# wi-fi.net
KiCad netlist of a schematic drawn in Altium Designer
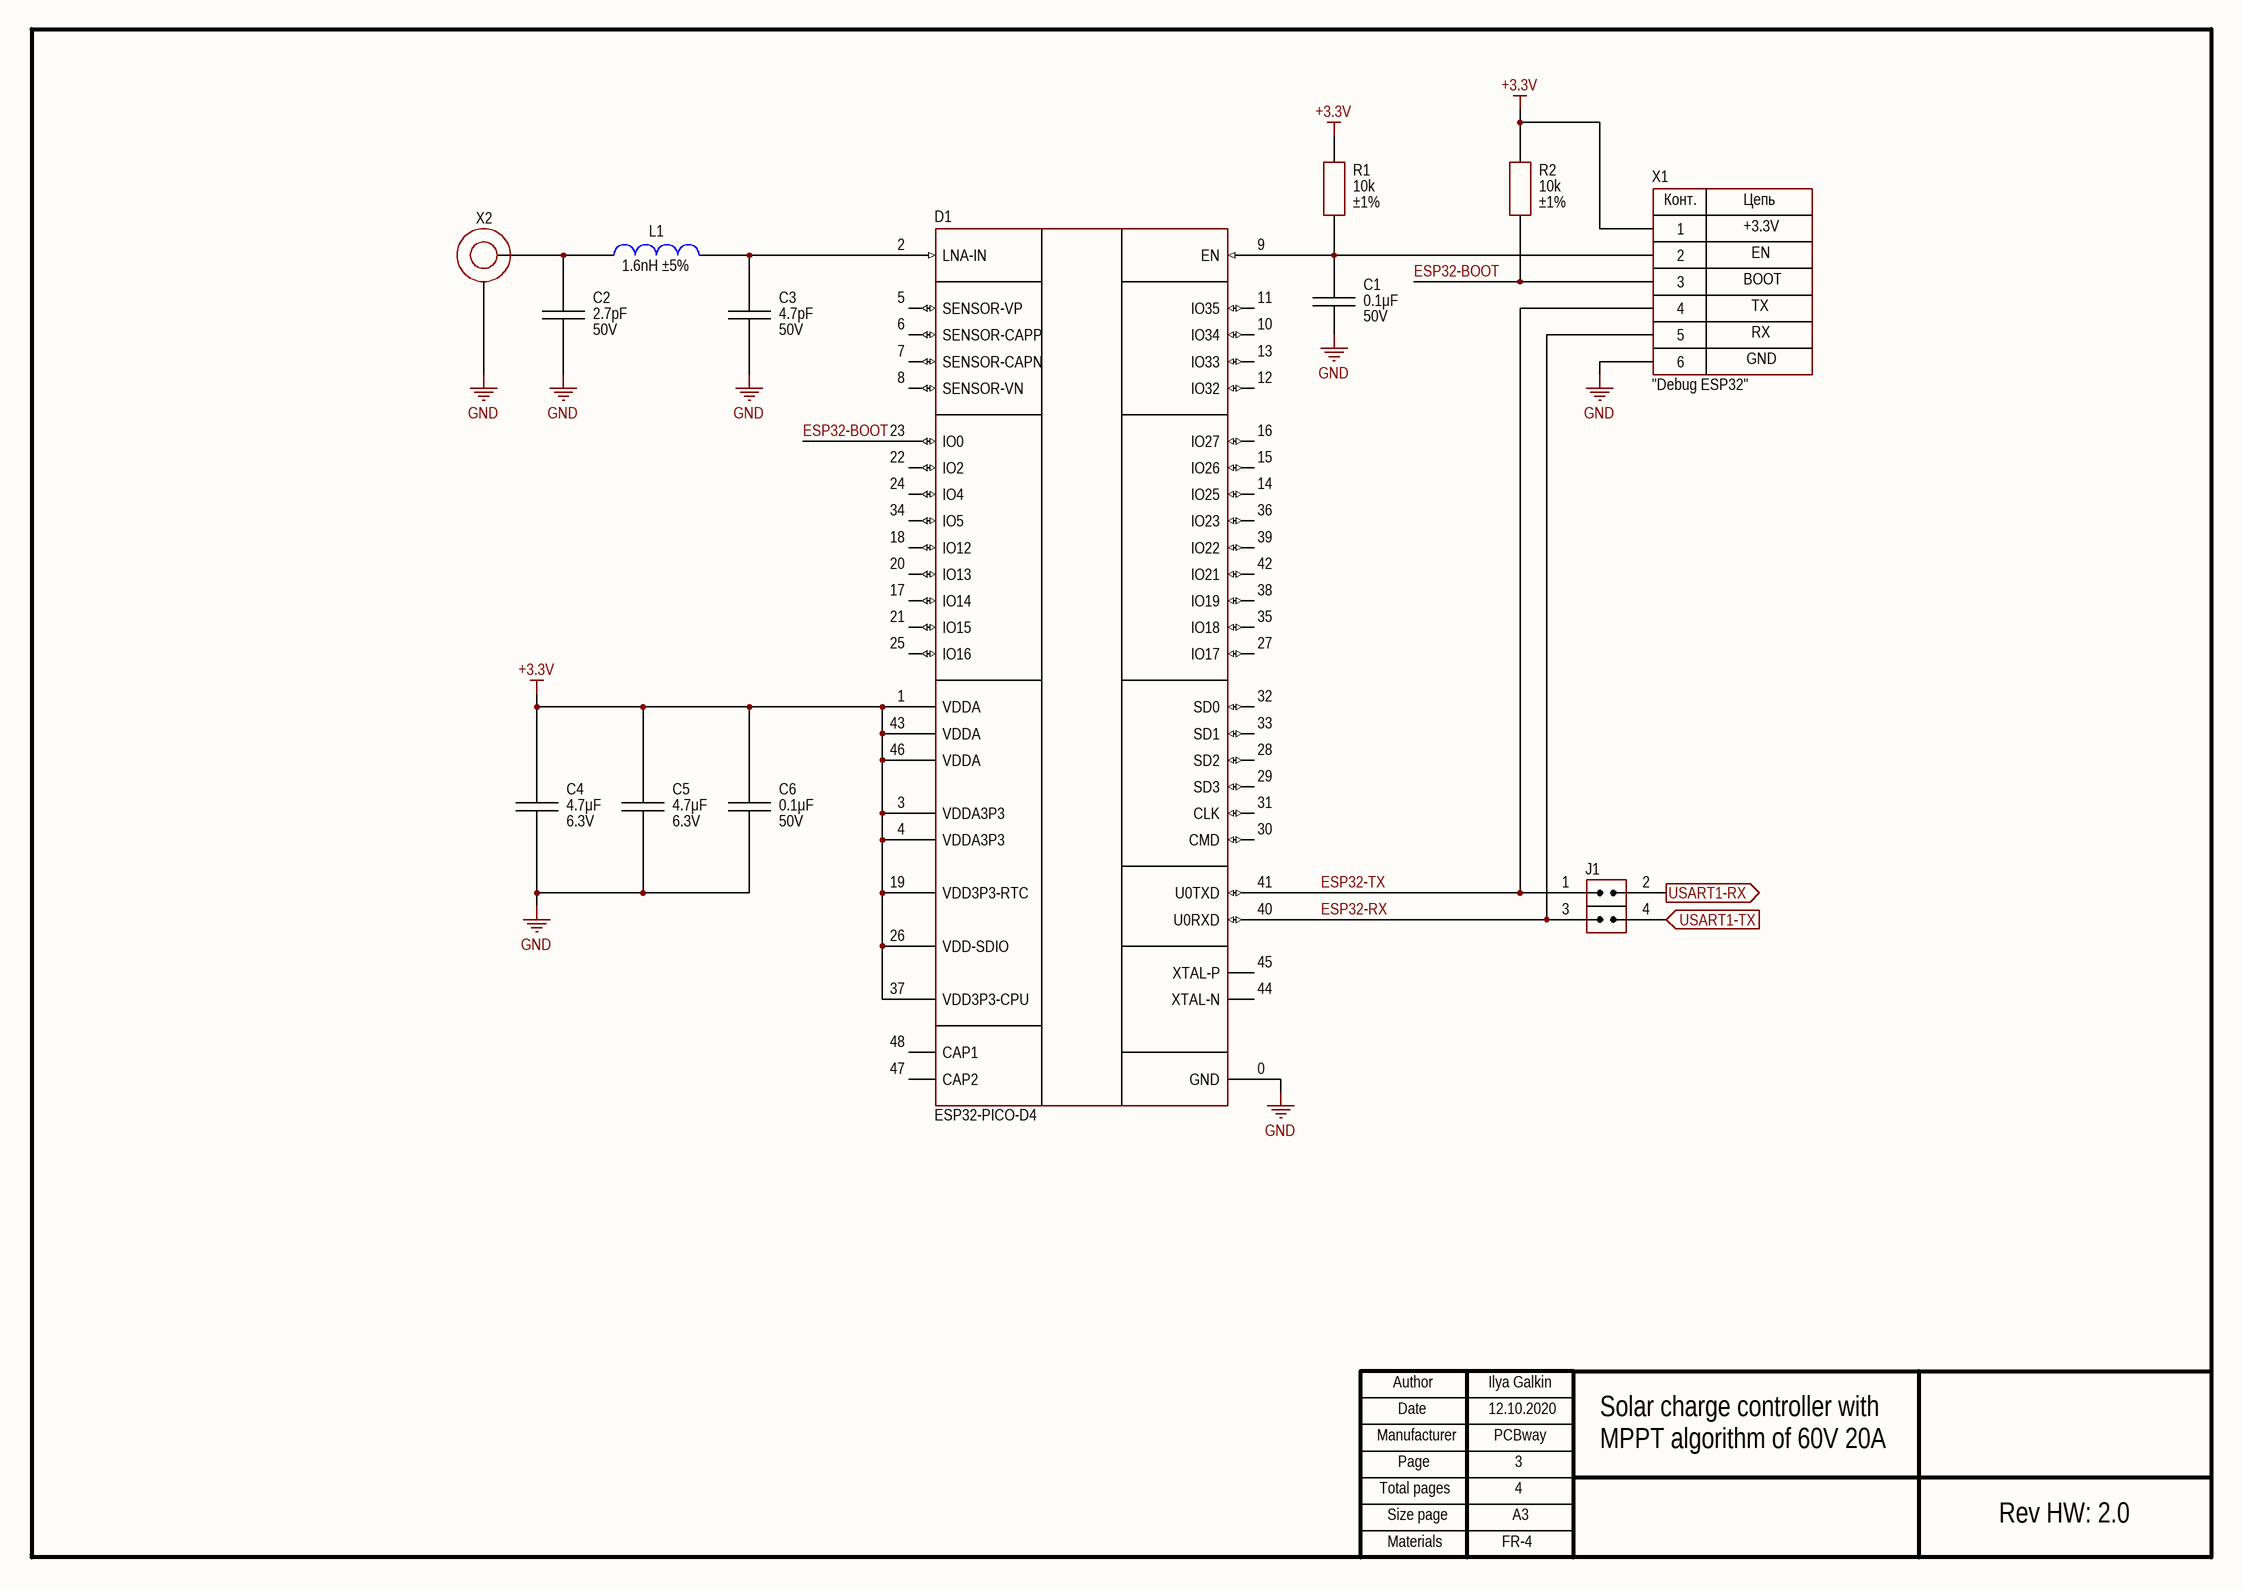
[diagram p0: wi-fi.SchDoc]

(export (version "E")
  (design (tool "Eeschema 10.0.6"))
  (components
    (comp (ref "C1")
      (value "0.1μF")
      (footprint "CAP: 0603")
      (fields
        (field (name "MANUFACTURER") "Samsung")
        (field (name "PARTNUMBER") "CL10B104KB8WPND")
        (field (name "VALUEMANUFACTURERPARTNUMBER") "Ceramic capacitor, 0.1μF, X7R, ±10%, 50V, 0603, -55...+125°C")
        (field (name "VOLTAGE") "50V")
      )
      (libsource (lib "Capacitor") (part "Ceramic_0603"))
    )
    (comp (ref "C2")
      (value "2.7pF")
      (footprint "CAP: 0603")
      (fields
        (field (name "MANUFACTURER") "Samsung")
        (field (name "PARTNUMBER") "CL10C2R7CB81PNC")
        (field (name "VALUEMANUFACTURERPARTNUMBER") "Ceramic capacitor, 2.7pF, NPO, ±0.25pF, 50V, 0603, -55...+125°C")
        (field (name "VOLTAGE") "50V")
      )
      (libsource (lib "capacitor") (part "Ceramic_0603"))
    )
    (comp (ref "C3")
      (value "4.7pF")
      (footprint "CAP: 0603")
      (fields
        (field (name "MANUFACTURER") "Samsung")
        (field (name "PARTNUMBER") "CL10C4R7BB8NNNC")
        (field (name "VALUEMANUFACTURERPARTNUMBER") "Ceramic capacitor, 4.7pF, NPO, ±0.1pF, 50V, 0603, -55...+125°C")
        (field (name "VOLTAGE") "50V")
      )
      (libsource (lib "capacitor") (part "Ceramic_0603"))
    )
    (comp (ref "C4")
      (value "4.7μF")
      (footprint "CAP: 0603")
      (fields
        (field (name "MANUFACTURER") "Samsung")
        (field (name "PARTNUMBER") "CL10B475KQ8NQNC")
        (field (name "VALUEMANUFACTURERPARTNUMBER") "Ceramic capacitor, 4.7μF, X7R, ±10%, 6.3V, 0603, -55...+125°C")
        (field (name "VOLTAGE") "6.3V")
      )
      (libsource (lib "Capacitor") (part "Ceramic_0603"))
    )
    (comp (ref "C5")
      (value "4.7μF")
      (footprint "CAP: 0603")
      (fields
        (field (name "MANUFACTURER") "Samsung")
        (field (name "PARTNUMBER") "CL10B475KQ8NQNC")
        (field (name "VALUEMANUFACTURERPARTNUMBER") "Ceramic capacitor, 4.7μF, X7R, ±10%, 6.3V, 0603, -55...+125°C")
        (field (name "VOLTAGE") "6.3V")
      )
      (libsource (lib "Capacitor") (part "Ceramic_0603"))
    )
    (comp (ref "C6")
      (value "0.1μF")
      (footprint "CAP: 0603")
      (fields
        (field (name "MANUFACTURER") "Samsung")
        (field (name "PARTNUMBER") "CL10B104KB8WPND")
        (field (name "VALUEMANUFACTURERPARTNUMBER") "Ceramic capacitor, 0.1μF, X7R, ±10%, 50V, 0603, -55...+125°C")
        (field (name "VOLTAGE") "50V")
      )
      (libsource (lib "Capacitor") (part "Ceramic_0603"))
    )
    (comp (ref "D1")
      (value "~")
      (footprint "48-LGA (7x7)")
      (description "Wi-Fi+BT")
      (fields (field (name "MANUFACTURER") "Espressif Systems") (field (name "PARTNUMBER") "ESP32-PICO-D4"))
      (libsource (lib "ic-rf-transceiver") (part "ESP32-PICO-D4"))
    )
    (comp (ref "J1")
      (value "~")
      (footprint "CON: JUMPER x2")
      (libsource (lib "connector") (part "Jumper_double"))
    )
    (comp (ref "L1")
      (value "1.6nH")
      (footprint "IND: 0603")
      (fields
        (field (name "MANUFACTURER") "Murata Electronics")
        (field (name "PARTNUMBER") "LQW18AS1N6J0ZD")
        (field (name "VALUEMANUFACTURERPARTNUMBER") "Fixed inductor, 1.6nH, ±5%, 0603, 700mA, -55...+125°C")
        (field (name "TOLERANCE") "±5%")
      )
      (libsource (lib "inductor") (part "Inductor_0603"))
    )
    (comp (ref "R1")
      (value "10k")
      (footprint "RES: 0603")
      (fields
        (field (name "MANUFACTURER") "Yageo")
        (field (name "PARTNUMBER") "AC0603FR-0710KL")
        (field (name "VALUEMANUFACTURERPARTNUMBER") "Resistor film, 10k, ±1%, 0603, 0.1W, -55...+125°C")
        (field (name "TOLERANCE") "±1%")
      )
      (libsource (lib "Resistor") (part "Resistor_0603"))
    )
    (comp (ref "R2")
      (value "10k")
      (footprint "RES: 0603")
      (fields
        (field (name "MANUFACTURER") "Yageo")
        (field (name "PARTNUMBER") "AC0603FR-0710KL")
        (field (name "VALUEMANUFACTURERPARTNUMBER") "Resistor film, 10k, ±1%, 0603, 0.1W, -55...+125°C")
        (field (name "TOLERANCE") "±1%")
      )
      (libsource (lib "Resistor") (part "Resistor_0603"))
    )
    (comp (ref "X1")
      (value "~")
      (footprint "CON: SM06B-GHS")
      (fields
        (field (name "MANUFACTURER") "JST")
        (field (name "VALUEMANUFACTURERPARTNUMBER") "Connector, 6pin, 1.25mm, 50VDC, 1A")
        (field (name "PARTNUMBER") "SM06B-GHS")
        (field (name "COMMENTTEXT") "\"Debug ESP32\"")
      )
      (libsource (lib "connector") (part "Connector_SM06B"))
    )
    (comp (ref "X2")
      (value "~")
      (footprint "CON: u.Fl")
      (fields
        (field (name "MANUFACTURER") "Hirose Electric")
        (field (name "VALUEMANUFACTURERPARTNUMBER") "Connector u.FL, 50 Ohm, 6GHz")
        (field (name "PARTNUMBER") "U.FL-R-SMT(01)")
      )
      (libsource (lib "connector") (part "Connector_uFL"))
    )
  )
  (nets
    (net (code "1") (name "+3.3V") (class "Default")
      (node (ref "C4") (pin "2") (pinfunction "2_2") (pintype "power_in"))
      (node (ref "C5") (pin "2") (pinfunction "2_2") (pintype "power_in"))
      (node (ref "C6") (pin "2") (pinfunction "2_2") (pintype "power_in"))
      (node (ref "D1") (pin "1") (pinfunction "VDDA_1") (pintype "passive"))
      (node (ref "D1") (pin "19") (pinfunction "VDD3P3-RTC_19") (pintype "passive"))
      (node (ref "D1") (pin "26") (pinfunction "VDD-SDIO_26") (pintype "passive"))
      (node (ref "D1") (pin "3") (pinfunction "VDDA3P3_3") (pintype "passive"))
      (node (ref "D1") (pin "37") (pinfunction "VDD3P3-CPU_37") (pintype "passive"))
      (node (ref "D1") (pin "4") (pinfunction "VDDA3P3_4") (pintype "passive"))
      (node (ref "D1") (pin "43") (pinfunction "VDDA_43") (pintype "passive"))
      (node (ref "D1") (pin "46") (pinfunction "VDDA_46") (pintype "passive"))
      (node (ref "R1") (pin "2") (pinfunction "2_2") (pintype "passive"))
      (node (ref "R2") (pin "2") (pinfunction "2_2") (pintype "passive"))
      (node (ref "X1") (pin "1") (pinfunction "1_1") (pintype "passive"))
    )
    (net (code "2") (name "/ESP32-BOOT") (class "Default")
      (node (ref "D1") (pin "23") (pinfunction "IO0_23") (pintype "bidirectional"))
      (node (ref "R2") (pin "1") (pinfunction "1_1") (pintype "passive"))
      (node (ref "X1") (pin "3") (pinfunction "3_3") (pintype "power_in"))
    )
    (net (code "3") (name "/ESP32-RX") (class "Default")
      (node (ref "D1") (pin "40") (pinfunction "U0RXD_40") (pintype "bidirectional"))
      (node (ref "J1") (pin "3") (pinfunction "IN_3") (pintype "passive"))
      (node (ref "X1") (pin "5") (pinfunction "5_5") (pintype "power_in"))
    )
    (net (code "4") (name "/ESP32-TX") (class "Default")
      (node (ref "D1") (pin "41") (pinfunction "U0TXD_41") (pintype "bidirectional"))
      (node (ref "J1") (pin "1") (pinfunction "IN_1") (pintype "passive"))
      (node (ref "X1") (pin "4") (pinfunction "4_4") (pintype "power_in"))
    )
    (net (code "5") (name "/USART1-RX") (class "Default")
      (node (ref "J1") (pin "2") (pinfunction "IN_2") (pintype "passive"))
    )
    (net (code "6") (name "/USART1-TX") (class "Default")
      (node (ref "J1") (pin "4") (pinfunction "IN_4") (pintype "passive"))
    )
    (net (code "7") (name "GND") (class "Default")
      (node (ref "C1") (pin "1") (pinfunction "1_1") (pintype "power_in"))
      (node (ref "C2") (pin "1") (pinfunction "1_1") (pintype "passive"))
      (node (ref "C3") (pin "1") (pinfunction "1_1") (pintype "passive"))
      (node (ref "C4") (pin "1") (pinfunction "1_1") (pintype "power_in"))
      (node (ref "C5") (pin "1") (pinfunction "1_1") (pintype "power_in"))
      (node (ref "C6") (pin "1") (pinfunction "1_1") (pintype "power_in"))
      (node (ref "D1") (pin "0") (pinfunction "GND_0") (pintype "passive"))
      (node (ref "X1") (pin "6") (pinfunction "6_6") (pintype "power_in"))
      (node (ref "X2") (pin "2") (pinfunction "2_2") (pintype "passive"))
    )
    (net (code "8") (name "Net-(C2-Pad2)") (class "Default")
      (node (ref "C2") (pin "2") (pinfunction "2_2") (pintype "passive"))
      (node (ref "L1") (pin "2") (pinfunction "2_2") (pintype "passive"))
      (node (ref "X2") (pin "1") (pinfunction "1_1") (pintype "passive"))
    )
    (net (code "9") (name "Net-(D1-EN)") (class "Default")
      (node (ref "C1") (pin "2") (pinfunction "2_2") (pintype "power_in"))
      (node (ref "D1") (pin "9") (pinfunction "EN_9") (pintype "input"))
      (node (ref "R1") (pin "1") (pinfunction "1_1") (pintype "passive"))
      (node (ref "X1") (pin "2") (pinfunction "2_2") (pintype "passive"))
    )
    (net (code "10") (name "Net-(D1-LNA-IN)") (class "Default")
      (node (ref "C3") (pin "2") (pinfunction "2_2") (pintype "passive"))
      (node (ref "D1") (pin "2") (pinfunction "LNA-IN_2") (pintype "input"))
      (node (ref "L1") (pin "1") (pinfunction "1_1") (pintype "passive"))
    )
    (net (code "11") (name "unconnected-(D1-CAP1-Pad48)") (class "Default")
      (node (ref "D1") (pin "48") (pinfunction "CAP1_48") (pintype "passive"))
    )
    (net (code "12") (name "unconnected-(D1-CAP2-Pad47)") (class "Default")
      (node (ref "D1") (pin "47") (pinfunction "CAP2_47") (pintype "passive"))
    )
    (net (code "13") (name "unconnected-(D1-CLK-Pad31)") (class "Default")
      (node (ref "D1") (pin "31") (pinfunction "CLK_31") (pintype "bidirectional"))
    )
    (net (code "14") (name "unconnected-(D1-CMD-Pad30)") (class "Default")
      (node (ref "D1") (pin "30") (pinfunction "CMD_30") (pintype "bidirectional"))
    )
    (net (code "15") (name "unconnected-(D1-IO2-Pad22)") (class "Default")
      (node (ref "D1") (pin "22") (pinfunction "IO2_22") (pintype "bidirectional"))
    )
    (net (code "16") (name "unconnected-(D1-IO4-Pad24)") (class "Default")
      (node (ref "D1") (pin "24") (pinfunction "IO4_24") (pintype "bidirectional"))
    )
    (net (code "17") (name "unconnected-(D1-IO5-Pad34)") (class "Default")
      (node (ref "D1") (pin "34") (pinfunction "IO5_34") (pintype "bidirectional"))
    )
    (net (code "18") (name "unconnected-(D1-IO12-Pad18)") (class "Default")
      (node (ref "D1") (pin "18") (pinfunction "IO12_18") (pintype "bidirectional"))
    )
    (net (code "19") (name "unconnected-(D1-IO13-Pad20)") (class "Default")
      (node (ref "D1") (pin "20") (pinfunction "IO13_20") (pintype "bidirectional"))
    )
    (net (code "20") (name "unconnected-(D1-IO14-Pad17)") (class "Default")
      (node (ref "D1") (pin "17") (pinfunction "IO14_17") (pintype "bidirectional"))
    )
    (net (code "21") (name "unconnected-(D1-IO15-Pad21)") (class "Default")
      (node (ref "D1") (pin "21") (pinfunction "IO15_21") (pintype "bidirectional"))
    )
    (net (code "22") (name "unconnected-(D1-IO16-Pad25)") (class "Default")
      (node (ref "D1") (pin "25") (pinfunction "IO16_25") (pintype "bidirectional"))
    )
    (net (code "23") (name "unconnected-(D1-IO17-Pad27)") (class "Default")
      (node (ref "D1") (pin "27") (pinfunction "IO17_27") (pintype "bidirectional"))
    )
    (net (code "24") (name "unconnected-(D1-IO18-Pad35)") (class "Default")
      (node (ref "D1") (pin "35") (pinfunction "IO18_35") (pintype "bidirectional"))
    )
    (net (code "25") (name "unconnected-(D1-IO19-Pad38)") (class "Default")
      (node (ref "D1") (pin "38") (pinfunction "IO19_38") (pintype "bidirectional"))
    )
    (net (code "26") (name "unconnected-(D1-IO21-Pad42)") (class "Default")
      (node (ref "D1") (pin "42") (pinfunction "IO21_42") (pintype "bidirectional"))
    )
    (net (code "27") (name "unconnected-(D1-IO22-Pad39)") (class "Default")
      (node (ref "D1") (pin "39") (pinfunction "IO22_39") (pintype "bidirectional"))
    )
    (net (code "28") (name "unconnected-(D1-IO23-Pad36)") (class "Default")
      (node (ref "D1") (pin "36") (pinfunction "IO23_36") (pintype "bidirectional"))
    )
    (net (code "29") (name "unconnected-(D1-IO25-Pad14)") (class "Default")
      (node (ref "D1") (pin "14") (pinfunction "IO25_14") (pintype "bidirectional"))
    )
    (net (code "30") (name "unconnected-(D1-IO26-Pad15)") (class "Default")
      (node (ref "D1") (pin "15") (pinfunction "IO26_15") (pintype "bidirectional"))
    )
    (net (code "31") (name "unconnected-(D1-IO27-Pad16)") (class "Default")
      (node (ref "D1") (pin "16") (pinfunction "IO27_16") (pintype "bidirectional"))
    )
    (net (code "32") (name "unconnected-(D1-IO32-Pad12)") (class "Default")
      (node (ref "D1") (pin "12") (pinfunction "IO32_12") (pintype "bidirectional"))
    )
    (net (code "33") (name "unconnected-(D1-IO33-Pad13)") (class "Default")
      (node (ref "D1") (pin "13") (pinfunction "IO33_13") (pintype "bidirectional"))
    )
    (net (code "34") (name "unconnected-(D1-IO34-Pad10)") (class "Default")
      (node (ref "D1") (pin "10") (pinfunction "IO34_10") (pintype "bidirectional"))
    )
    (net (code "35") (name "unconnected-(D1-IO35-Pad11)") (class "Default")
      (node (ref "D1") (pin "11") (pinfunction "IO35_11") (pintype "bidirectional"))
    )
    (net (code "36") (name "unconnected-(D1-SD0-Pad32)") (class "Default")
      (node (ref "D1") (pin "32") (pinfunction "SD0_32") (pintype "bidirectional"))
    )
    (net (code "37") (name "unconnected-(D1-SD1-Pad33)") (class "Default")
      (node (ref "D1") (pin "33") (pinfunction "SD1_33") (pintype "bidirectional"))
    )
    (net (code "38") (name "unconnected-(D1-SD2-Pad28)") (class "Default")
      (node (ref "D1") (pin "28") (pinfunction "SD2_28") (pintype "bidirectional"))
    )
    (net (code "39") (name "unconnected-(D1-SD3-Pad29)") (class "Default")
      (node (ref "D1") (pin "29") (pinfunction "SD3_29") (pintype "bidirectional"))
    )
    (net (code "40") (name "unconnected-(D1-SENSOR-CAPN-Pad7)") (class "Default")
      (node (ref "D1") (pin "7") (pinfunction "SENSOR-CAPN_7") (pintype "bidirectional"))
    )
    (net (code "41") (name "unconnected-(D1-SENSOR-CAPP-Pad6)") (class "Default")
      (node (ref "D1") (pin "6") (pinfunction "SENSOR-CAPP_6") (pintype "bidirectional"))
    )
    (net (code "42") (name "unconnected-(D1-SENSOR-VN-Pad8)") (class "Default")
      (node (ref "D1") (pin "8") (pinfunction "SENSOR-VN_8") (pintype "bidirectional"))
    )
    (net (code "43") (name "unconnected-(D1-SENSOR-VP-Pad5)") (class "Default")
      (node (ref "D1") (pin "5") (pinfunction "SENSOR-VP_5") (pintype "bidirectional"))
    )
    (net (code "44") (name "unconnected-(D1-XTAL-N-Pad44)") (class "Default")
      (node (ref "D1") (pin "44") (pinfunction "XTAL-N_44") (pintype "passive"))
    )
    (net (code "45") (name "unconnected-(D1-XTAL-P-Pad45)") (class "Default")
      (node (ref "D1") (pin "45") (pinfunction "XTAL-P_45") (pintype "passive"))
    )
  )
)
